# Handheld.net
KiCad netlist of a schematic drawn in EAGLE
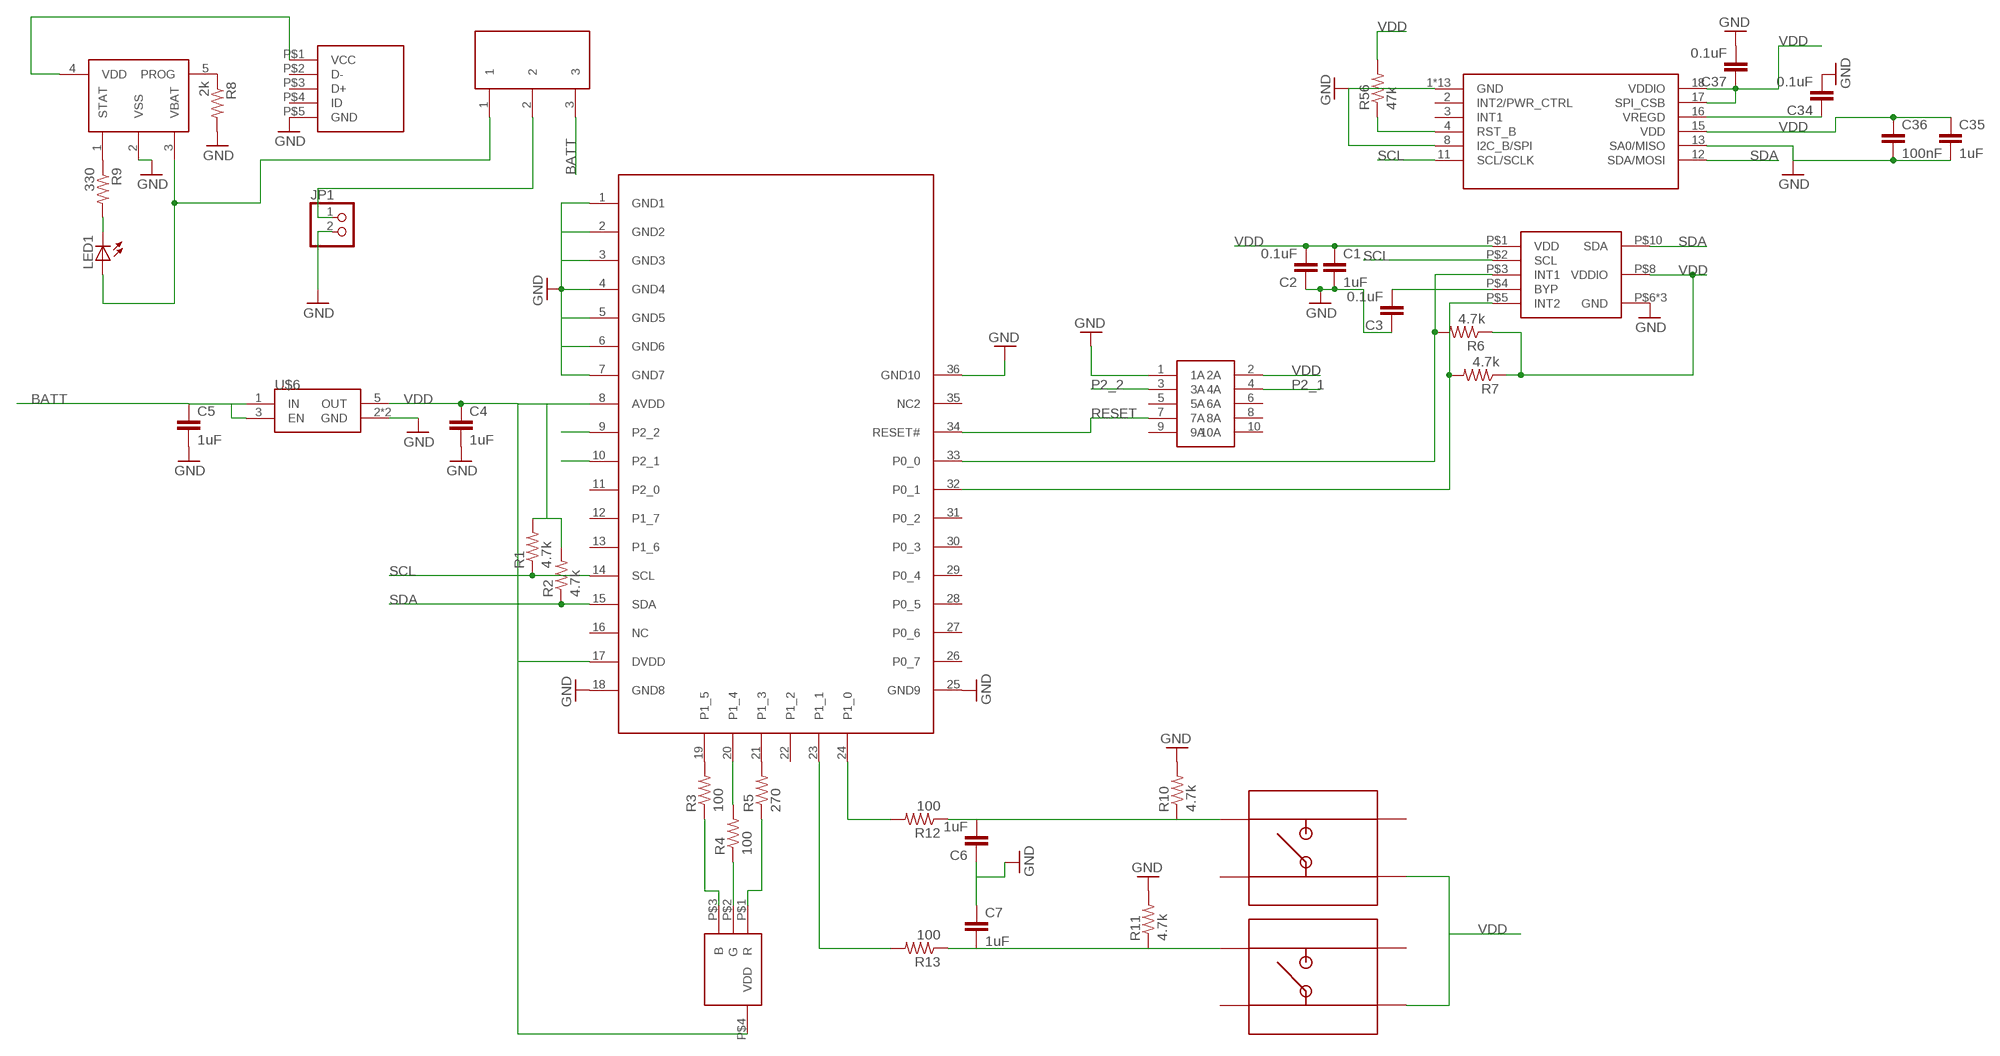
[diagram p0: schematic, sheet 1]

(export (version "E")
  (design (tool "Eeschema 10.0.6"))
  (components
    (comp (ref "C1")
      (value "1uF")
      (footprint "eagle-import:C0402")
      (libsource (lib "eagle-import") (part "C-EUC0402"))
    )
    (comp (ref "C2")
      (value "0.1uF")
      (footprint "eagle-import:C0402")
      (libsource (lib "eagle-import") (part "C-EUC0402"))
    )
    (comp (ref "C3")
      (value "0.1uF")
      (footprint "eagle-import:C0402")
      (libsource (lib "eagle-import") (part "C-EUC0402"))
    )
    (comp (ref "C4")
      (value "1uF")
      (footprint "eagle-import:C0402")
      (libsource (lib "eagle-import") (part "C-EUC0402"))
    )
    (comp (ref "C5")
      (value "1uF")
      (footprint "eagle-import:C0402")
      (libsource (lib "eagle-import") (part "C-EUC0402"))
    )
    (comp (ref "C6")
      (value "1uF")
      (footprint "eagle-import:C0402")
      (libsource (lib "eagle-import") (part "C-EUC0402"))
    )
    (comp (ref "C7")
      (value "1uF")
      (footprint "eagle-import:C0402")
      (libsource (lib "eagle-import") (part "C-EUC0402"))
    )
    (comp (ref "C34")
      (value "0.1uF")
      (footprint "eagle-import:C0402")
      (libsource (lib "eagle-import") (part "C-EUC0402"))
    )
    (comp (ref "C35")
      (value "1uF")
      (footprint "eagle-import:C0402")
      (libsource (lib "eagle-import") (part "C-EUC0402"))
    )
    (comp (ref "C36")
      (value "100nF")
      (footprint "eagle-import:C0402")
      (libsource (lib "eagle-import") (part "C-EUC0402"))
    )
    (comp (ref "C37")
      (value "0.1uF")
      (footprint "eagle-import:C0402")
      (libsource (lib "eagle-import") (part "C-EUC0402"))
    )
    (comp (ref "JP1")
      (value "PINHD-1X2")
      (footprint "eagle-import:1X02")
      (libsource (lib "eagle-import") (part "PINHD-1X2"))
    )
    (comp (ref "LED1")
      (value "LEDCHIPLED_0805")
      (footprint "eagle-import:CHIPLED_0805")
      (libsource (lib "eagle-import") (part "LEDCHIPLED_0805"))
    )
    (comp (ref "R1")
      (value "4.7k")
      (footprint "eagle-import:R0402")
      (libsource (lib "eagle-import") (part "R-US_R0402"))
    )
    (comp (ref "R2")
      (value "4.7k")
      (footprint "eagle-import:R0402")
      (libsource (lib "eagle-import") (part "R-US_R0402"))
    )
    (comp (ref "R3")
      (value "100")
      (footprint "eagle-import:R0402")
      (libsource (lib "eagle-import") (part "R-US_R0402"))
    )
    (comp (ref "R4")
      (value "100")
      (footprint "eagle-import:R0402")
      (libsource (lib "eagle-import") (part "R-US_R0402"))
    )
    (comp (ref "R5")
      (value "270")
      (footprint "eagle-import:R0402")
      (libsource (lib "eagle-import") (part "R-US_R0402"))
    )
    (comp (ref "R6")
      (value "4.7k")
      (footprint "eagle-import:R0402")
      (libsource (lib "eagle-import") (part "R-US_R0402"))
    )
    (comp (ref "R7")
      (value "4.7k")
      (footprint "eagle-import:R0402")
      (libsource (lib "eagle-import") (part "R-US_R0402"))
    )
    (comp (ref "R8")
      (value "2k")
      (footprint "eagle-import:R0402")
      (libsource (lib "eagle-import") (part "R-US_R0402"))
    )
    (comp (ref "R9")
      (value "330")
      (footprint "eagle-import:R0402")
      (libsource (lib "eagle-import") (part "R-US_R0402"))
    )
    (comp (ref "R10")
      (value "4.7k")
      (footprint "eagle-import:R0402")
      (libsource (lib "eagle-import") (part "R-US_R0402"))
    )
    (comp (ref "R11")
      (value "4.7k")
      (footprint "eagle-import:R0402")
      (libsource (lib "eagle-import") (part "R-US_R0402"))
    )
    (comp (ref "R12")
      (value "100")
      (footprint "eagle-import:R0402")
      (libsource (lib "eagle-import") (part "R-US_R0402"))
    )
    (comp (ref "R13")
      (value "100")
      (footprint "eagle-import:R0402")
      (libsource (lib "eagle-import") (part "R-US_R0402"))
    )
    (comp (ref "R56")
      (value "47k")
      (footprint "eagle-import:R0402")
      (libsource (lib "eagle-import") (part "R-US_R0402"))
    )
    (comp (ref "U$1")
      (value "BLE113")
      (footprint "eagle-import:BLUEGIGA")
      (libsource (lib "eagle-import") (part "BLE113"))
    )
    (comp (ref "U$2")
      (value "RIBBON_10POS_MALE")
      (footprint "eagle-import:RIBBON_10POS_MALE")
      (libsource (lib "eagle-import") (part "RIBBON_10POS_MALE"))
    )
    (comp (ref "U$3")
      (value "MMA8653FC")
      (footprint "eagle-import:10-DFN2X2")
      (libsource (lib "eagle-import") (part "MMA8653FC"))
    )
    (comp (ref "U$4")
      (value "MCP73831")
      (footprint "eagle-import:MCP73831")
      (libsource (lib "eagle-import") (part "MCP73831"))
    )
    (comp (ref "U$5")
      (value "MICRO_USB")
      (footprint "eagle-import:MOLEX_USB")
      (libsource (lib "eagle-import") (part "MICRO_USB"))
    )
    (comp (ref "U$6")
      (value "TPS782XX")
      (footprint "eagle-import:SOT23-5L")
      (libsource (lib "eagle-import") (part "TPS782XX"))
    )
    (comp (ref "U$7")
      (value "LTST-C19HE1WT")
      (footprint "eagle-import:LTST-C19HE1WT")
      (libsource (lib "eagle-import") (part "LTST-C19HE1WT"))
    )
    (comp (ref "U$8")
      (value "SMD_TACTILE")
      (footprint "eagle-import:EVQ-Q2U03W")
      (libsource (lib "eagle-import") (part "SMD_TACTILE"))
    )
    (comp (ref "U$9")
      (value "SMD_TACTILE")
      (footprint "eagle-import:EVQ-Q2U03W")
      (libsource (lib "eagle-import") (part "SMD_TACTILE"))
    )
    (comp (ref "U$10")
      (value "SPDT_THRU")
      (footprint "eagle-import:SPDT_THRU")
      (libsource (lib "eagle-import") (part "SPDT_THRU"))
    )
    (comp (ref "U$34")
      (value "FXAS21002")
      (footprint "eagle-import:FXAS21002")
      (libsource (lib "eagle-import") (part "FXAS21002"))
    )
  )
  (nets
    (net (code "1") (name "/BATT") (class "Default")
      (node (ref "C5") (pin "1") (pinfunction "1_1") (pintype "passive"))
      (node (ref "U$10") (pin "3") (pinfunction "3_3") (pintype "bidirectional"))
      (node (ref "U$6") (pin "1") (pinfunction "IN_1") (pintype "bidirectional"))
      (node (ref "U$6") (pin "3") (pinfunction "EN_3") (pintype "bidirectional"))
    )
    (net (code "2") (name "/P2_1") (class "Default")
      (node (ref "U$2") (pin "4") (pinfunction "4A_4") (pintype "bidirectional"))
    )
    (net (code "3") (name "/P2_2") (class "Default")
      (node (ref "U$2") (pin "3") (pinfunction "3A_3") (pintype "bidirectional"))
    )
    (net (code "4") (name "/RESET") (class "Default")
      (node (ref "U$1") (pin "34") (pinfunction "RESET#_34") (pintype "bidirectional"))
      (node (ref "U$2") (pin "7") (pinfunction "7A_7") (pintype "bidirectional"))
    )
    (net (code "5") (name "/SCL") (class "Default")
      (node (ref "R1") (pin "1") (pinfunction "1_1") (pintype "passive"))
      (node (ref "U$1") (pin "14") (pinfunction "SCL_14") (pintype "bidirectional"))
      (node (ref "U$3") (pin "P$2") (pinfunction "SCL_P$2") (pintype "bidirectional"))
      (node (ref "U$34") (pin "11") (pinfunction "SCL/SCLK_11") (pintype "bidirectional"))
    )
    (net (code "6") (name "/SDA") (class "Default")
      (node (ref "R2") (pin "1") (pinfunction "1_1") (pintype "passive"))
      (node (ref "U$1") (pin "15") (pinfunction "SDA_15") (pintype "bidirectional"))
      (node (ref "U$3") (pin "P$10") (pinfunction "SDA_P$10") (pintype "bidirectional"))
      (node (ref "U$34") (pin "12") (pinfunction "SDA/MOSI_12") (pintype "bidirectional"))
    )
    (net (code "7") (name "/VDD") (class "Default")
      (node (ref "C1") (pin "1") (pinfunction "1_1") (pintype "passive"))
      (node (ref "C2") (pin "2") (pinfunction "2_2") (pintype "passive"))
      (node (ref "C35") (pin "1") (pinfunction "1_1") (pintype "passive"))
      (node (ref "C36") (pin "1") (pinfunction "1_1") (pintype "passive"))
      (node (ref "C37") (pin "1") (pinfunction "1_1") (pintype "passive"))
      (node (ref "C4") (pin "1") (pinfunction "1_1") (pintype "passive"))
      (node (ref "R1") (pin "2") (pinfunction "2_2") (pintype "passive"))
      (node (ref "R2") (pin "2") (pinfunction "2_2") (pintype "passive"))
      (node (ref "R56") (pin "2") (pinfunction "2_2") (pintype "passive"))
      (node (ref "R6") (pin "1") (pinfunction "1_1") (pintype "passive"))
      (node (ref "R7") (pin "1") (pinfunction "1_1") (pintype "passive"))
      (node (ref "U$1") (pin "17") (pinfunction "DVDD_17") (pintype "bidirectional"))
      (node (ref "U$1") (pin "8") (pinfunction "AVDD_8") (pintype "bidirectional"))
      (node (ref "U$2") (pin "2") (pinfunction "2A_2") (pintype "bidirectional"))
      (node (ref "U$3") (pin "P$1") (pinfunction "VDD_P$1") (pintype "bidirectional"))
      (node (ref "U$3") (pin "P$8") (pinfunction "VDDIO_P$8") (pintype "bidirectional"))
      (node (ref "U$34") (pin "15") (pinfunction "VDD_15") (pintype "bidirectional"))
      (node (ref "U$34") (pin "17") (pinfunction "SPI_CSB_17") (pintype "bidirectional"))
      (node (ref "U$34") (pin "18") (pinfunction "VDDIO_18") (pintype "bidirectional"))
      (node (ref "U$6") (pin "5") (pinfunction "OUT_5") (pintype "bidirectional"))
      (node (ref "U$7") (pin "P$4") (pinfunction "VDD_P$4") (pintype "bidirectional"))
      (node (ref "U$8") (pin "4") (pinfunction "4_4") (pintype "bidirectional"))
      (node (ref "U$9") (pin "4") (pinfunction "4_4") (pintype "bidirectional"))
    )
    (net (code "8") (name "GND") (class "Default")
      (node (ref "C1") (pin "2") (pinfunction "2_2") (pintype "passive"))
      (node (ref "C2") (pin "1") (pinfunction "1_1") (pintype "passive"))
      (node (ref "C3") (pin "1") (pinfunction "1_1") (pintype "passive"))
      (node (ref "C34") (pin "2") (pinfunction "2_2") (pintype "passive"))
      (node (ref "C35") (pin "2") (pinfunction "2_2") (pintype "passive"))
      (node (ref "C36") (pin "2") (pinfunction "2_2") (pintype "passive"))
      (node (ref "C37") (pin "2") (pinfunction "2_2") (pintype "passive"))
      (node (ref "C4") (pin "2") (pinfunction "2_2") (pintype "passive"))
      (node (ref "C5") (pin "2") (pinfunction "2_2") (pintype "passive"))
      (node (ref "C6") (pin "1") (pinfunction "1_1") (pintype "passive"))
      (node (ref "C7") (pin "1") (pinfunction "1_1") (pintype "passive"))
      (node (ref "JP1") (pin "2") (pinfunction "2_2") (pintype "passive"))
      (node (ref "R10") (pin "2") (pinfunction "2_2") (pintype "passive"))
      (node (ref "R11") (pin "2") (pinfunction "2_2") (pintype "passive"))
      (node (ref "R8") (pin "2") (pinfunction "2_2") (pintype "passive"))
      (node (ref "U$1") (pin "1") (pinfunction "GND1_1") (pintype "bidirectional"))
      (node (ref "U$1") (pin "18") (pinfunction "GND8_18") (pintype "bidirectional"))
      (node (ref "U$1") (pin "2") (pinfunction "GND2_2") (pintype "bidirectional"))
      (node (ref "U$1") (pin "25") (pinfunction "GND9_25") (pintype "bidirectional"))
      (node (ref "U$1") (pin "3") (pinfunction "GND3_3") (pintype "bidirectional"))
      (node (ref "U$1") (pin "36") (pinfunction "GND10_36") (pintype "bidirectional"))
      (node (ref "U$1") (pin "4") (pinfunction "GND4_4") (pintype "bidirectional"))
      (node (ref "U$1") (pin "5") (pinfunction "GND5_5") (pintype "bidirectional"))
      (node (ref "U$1") (pin "6") (pinfunction "GND6_6") (pintype "bidirectional"))
      (node (ref "U$1") (pin "7") (pinfunction "GND7_7") (pintype "bidirectional"))
      (node (ref "U$2") (pin "1") (pinfunction "1A_1") (pintype "bidirectional"))
      (node (ref "U$3") (pin "P$6") (pinfunction "GND_P$6") (pintype "bidirectional"))
      (node (ref "U$3") (pin "P$7") (pinfunction "GND_P$7") (pintype "bidirectional"))
      (node (ref "U$3") (pin "P$9") (pinfunction "GND_P$9") (pintype "bidirectional"))
      (node (ref "U$34") (pin "1") (pinfunction "GND_1") (pintype "bidirectional"))
      (node (ref "U$34") (pin "10") (pinfunction "GND_10") (pintype "bidirectional"))
      (node (ref "U$34") (pin "13") (pinfunction "SA0/MISO_13") (pintype "bidirectional"))
      (node (ref "U$34") (pin "14") (pinfunction "GND_14") (pintype "bidirectional"))
      (node (ref "U$34") (pin "19") (pinfunction "GND_19") (pintype "bidirectional"))
      (node (ref "U$34") (pin "20") (pinfunction "GND_20") (pintype "bidirectional"))
      (node (ref "U$34") (pin "21") (pinfunction "GND_21") (pintype "bidirectional"))
      (node (ref "U$34") (pin "22") (pinfunction "GND_22") (pintype "bidirectional"))
      (node (ref "U$34") (pin "23") (pinfunction "GND_23") (pintype "bidirectional"))
      (node (ref "U$34") (pin "24") (pinfunction "GND_24") (pintype "bidirectional"))
      (node (ref "U$34") (pin "5") (pinfunction "GND_5") (pintype "bidirectional"))
      (node (ref "U$34") (pin "6") (pinfunction "GND_6") (pintype "bidirectional"))
      (node (ref "U$34") (pin "7") (pinfunction "GND_7") (pintype "bidirectional"))
      (node (ref "U$34") (pin "8") (pinfunction "I2C_B/SPI_8") (pintype "bidirectional"))
      (node (ref "U$34") (pin "9") (pinfunction "GND_9") (pintype "bidirectional"))
      (node (ref "U$4") (pin "2") (pinfunction "VSS_2") (pintype "bidirectional"))
      (node (ref "U$5") (pin "P$5") (pinfunction "GND_P$5") (pintype "bidirectional"))
      (node (ref "U$6") (pin "2") (pinfunction "GND_2") (pintype "bidirectional"))
      (node (ref "U$6") (pin "4") (pinfunction "GND_4") (pintype "bidirectional"))
    )
    (net (code "9") (name "Net-(C6-Pad2)") (class "Default")
      (node (ref "C6") (pin "2") (pinfunction "2_2") (pintype "passive"))
      (node (ref "R10") (pin "1") (pinfunction "1_1") (pintype "passive"))
      (node (ref "R12") (pin "1") (pinfunction "1_1") (pintype "passive"))
      (node (ref "U$8") (pin "1") (pinfunction "1_1") (pintype "bidirectional"))
    )
    (net (code "10") (name "Net-(C7-Pad2)") (class "Default")
      (node (ref "C7") (pin "2") (pinfunction "2_2") (pintype "passive"))
      (node (ref "R11") (pin "1") (pinfunction "1_1") (pintype "passive"))
      (node (ref "R13") (pin "1") (pinfunction "1_1") (pintype "passive"))
      (node (ref "U$9") (pin "1") (pinfunction "1_1") (pintype "bidirectional"))
    )
    (net (code "11") (name "Net-(JP1-Pad1)") (class "Default")
      (node (ref "JP1") (pin "1") (pinfunction "1_1") (pintype "passive"))
      (node (ref "U$10") (pin "2") (pinfunction "2_2") (pintype "bidirectional"))
    )
    (net (code "12") (name "Net-(LED1-PadC)") (class "Default")
      (node (ref "LED1") (pin "C") (pinfunction "C_C") (pintype "passive"))
      (node (ref "R9") (pin "2") (pinfunction "2_2") (pintype "passive"))
    )
    (net (code "13") (name "Net-(U$1-P0_0)") (class "Default")
      (node (ref "R6") (pin "2") (pinfunction "2_2") (pintype "passive"))
      (node (ref "U$1") (pin "33") (pinfunction "P0_0_33") (pintype "bidirectional"))
      (node (ref "U$3") (pin "P$3") (pinfunction "INT1_P$3") (pintype "bidirectional"))
    )
    (net (code "14") (name "Net-(U$1-P0_1)") (class "Default")
      (node (ref "R7") (pin "2") (pinfunction "2_2") (pintype "passive"))
      (node (ref "U$1") (pin "32") (pinfunction "P0_1_32") (pintype "bidirectional"))
      (node (ref "U$3") (pin "P$5") (pinfunction "INT2_P$5") (pintype "bidirectional"))
    )
    (net (code "15") (name "Net-(U$1-P1_0)") (class "Default")
      (node (ref "R12") (pin "2") (pinfunction "2_2") (pintype "passive"))
      (node (ref "U$1") (pin "24") (pinfunction "P1_0_24") (pintype "bidirectional"))
    )
    (net (code "16") (name "Net-(U$1-P1_1)") (class "Default")
      (node (ref "R13") (pin "2") (pinfunction "2_2") (pintype "passive"))
      (node (ref "U$1") (pin "23") (pinfunction "P1_1_23") (pintype "bidirectional"))
    )
    (net (code "17") (name "Net-(U$1-P1_3)") (class "Default")
      (node (ref "R5") (pin "2") (pinfunction "2_2") (pintype "passive"))
      (node (ref "U$1") (pin "21") (pinfunction "P1_3_21") (pintype "bidirectional"))
    )
    (net (code "18") (name "Net-(U$1-P1_4)") (class "Default")
      (node (ref "R4") (pin "2") (pinfunction "2_2") (pintype "passive"))
      (node (ref "U$1") (pin "20") (pinfunction "P1_4_20") (pintype "bidirectional"))
    )
    (net (code "19") (name "Net-(U$1-P1_5)") (class "Default")
      (node (ref "R3") (pin "2") (pinfunction "2_2") (pintype "passive"))
      (node (ref "U$1") (pin "19") (pinfunction "P1_5_19") (pintype "bidirectional"))
    )
    (net (code "20") (name "Net-(U$3-BYP)") (class "Default")
      (node (ref "C3") (pin "2") (pinfunction "2_2") (pintype "passive"))
      (node (ref "U$3") (pin "P$4") (pinfunction "BYP_P$4") (pintype "bidirectional"))
    )
    (net (code "21") (name "Net-(U$4-PROG)") (class "Default")
      (node (ref "R8") (pin "1") (pinfunction "1_1") (pintype "passive"))
      (node (ref "U$4") (pin "5") (pinfunction "PROG_5") (pintype "bidirectional"))
    )
    (net (code "22") (name "Net-(U$4-STAT)") (class "Default")
      (node (ref "R9") (pin "1") (pinfunction "1_1") (pintype "passive"))
      (node (ref "U$4") (pin "1") (pinfunction "STAT_1") (pintype "bidirectional"))
    )
    (net (code "23") (name "Net-(U$4-VBAT)") (class "Default")
      (node (ref "LED1") (pin "A") (pinfunction "A_A") (pintype "passive"))
      (node (ref "U$10") (pin "1") (pinfunction "1_1") (pintype "bidirectional"))
      (node (ref "U$4") (pin "3") (pinfunction "VBAT_3") (pintype "bidirectional"))
    )
    (net (code "24") (name "Net-(U$4-VDD)") (class "Default")
      (node (ref "U$4") (pin "4") (pinfunction "VDD_4") (pintype "bidirectional"))
      (node (ref "U$5") (pin "P$1") (pinfunction "VCC_P$1") (pintype "bidirectional"))
    )
    (net (code "25") (name "Net-(U$7-B)") (class "Default")
      (node (ref "R3") (pin "1") (pinfunction "1_1") (pintype "passive"))
      (node (ref "U$7") (pin "P$3") (pinfunction "B_P$3") (pintype "bidirectional"))
    )
    (net (code "26") (name "Net-(U$7-G)") (class "Default")
      (node (ref "R4") (pin "1") (pinfunction "1_1") (pintype "passive"))
      (node (ref "U$7") (pin "P$2") (pinfunction "G_P$2") (pintype "bidirectional"))
    )
    (net (code "27") (name "Net-(U$7-R)") (class "Default")
      (node (ref "R5") (pin "1") (pinfunction "1_1") (pintype "passive"))
      (node (ref "U$7") (pin "P$1") (pinfunction "R_P$1") (pintype "bidirectional"))
    )
    (net (code "28") (name "Net-(U$34-RST_B)") (class "Default")
      (node (ref "R56") (pin "1") (pinfunction "1_1") (pintype "passive"))
      (node (ref "U$34") (pin "4") (pinfunction "RST_B_4") (pintype "bidirectional"))
    )
    (net (code "29") (name "Net-(U$34-VREGD)") (class "Default")
      (node (ref "C34") (pin "1") (pinfunction "1_1") (pintype "passive"))
      (node (ref "U$34") (pin "16") (pinfunction "VREGD_16") (pintype "bidirectional"))
    )
    (net (code "30") (name "unconnected-(U$1-NC-Pad16)") (class "Default")
      (node (ref "U$1") (pin "16") (pinfunction "NC_16") (pintype "bidirectional"))
    )
    (net (code "31") (name "unconnected-(U$1-NC2-Pad35)") (class "Default")
      (node (ref "U$1") (pin "35") (pinfunction "NC2_35") (pintype "bidirectional"))
    )
    (net (code "32") (name "unconnected-(U$1-P0_2-Pad31)") (class "Default")
      (node (ref "U$1") (pin "31") (pinfunction "P0_2_31") (pintype "bidirectional"))
    )
    (net (code "33") (name "unconnected-(U$1-P0_3-Pad30)") (class "Default")
      (node (ref "U$1") (pin "30") (pinfunction "P0_3_30") (pintype "bidirectional"))
    )
    (net (code "34") (name "unconnected-(U$1-P0_4-Pad29)") (class "Default")
      (node (ref "U$1") (pin "29") (pinfunction "P0_4_29") (pintype "bidirectional"))
    )
    (net (code "35") (name "unconnected-(U$1-P0_5-Pad28)") (class "Default")
      (node (ref "U$1") (pin "28") (pinfunction "P0_5_28") (pintype "bidirectional"))
    )
    (net (code "36") (name "unconnected-(U$1-P0_6-Pad27)") (class "Default")
      (node (ref "U$1") (pin "27") (pinfunction "P0_6_27") (pintype "bidirectional"))
    )
    (net (code "37") (name "unconnected-(U$1-P0_7-Pad26)") (class "Default")
      (node (ref "U$1") (pin "26") (pinfunction "P0_7_26") (pintype "bidirectional"))
    )
    (net (code "38") (name "unconnected-(U$1-P1_2-Pad22)") (class "Default")
      (node (ref "U$1") (pin "22") (pinfunction "P1_2_22") (pintype "bidirectional"))
    )
    (net (code "39") (name "unconnected-(U$1-P1_6-Pad13)") (class "Default")
      (node (ref "U$1") (pin "13") (pinfunction "P1_6_13") (pintype "bidirectional"))
    )
    (net (code "40") (name "unconnected-(U$1-P1_7-Pad12)") (class "Default")
      (node (ref "U$1") (pin "12") (pinfunction "P1_7_12") (pintype "bidirectional"))
    )
    (net (code "41") (name "unconnected-(U$1-P2_0-Pad11)") (class "Default")
      (node (ref "U$1") (pin "11") (pinfunction "P2_0_11") (pintype "bidirectional"))
    )
    (net (code "42") (name "unconnected-(U$1-P2_1-Pad10)") (class "Default")
      (node (ref "U$1") (pin "10") (pinfunction "P2_1_10") (pintype "bidirectional"))
    )
    (net (code "43") (name "unconnected-(U$1-P2_2-Pad9)") (class "Default")
      (node (ref "U$1") (pin "9") (pinfunction "P2_2_9") (pintype "bidirectional"))
    )
    (net (code "44") (name "unconnected-(U$2-5A-Pad5)") (class "Default")
      (node (ref "U$2") (pin "5") (pinfunction "5A_5") (pintype "bidirectional"))
    )
    (net (code "45") (name "unconnected-(U$2-6A-Pad6)") (class "Default")
      (node (ref "U$2") (pin "6") (pinfunction "6A_6") (pintype "bidirectional"))
    )
    (net (code "46") (name "unconnected-(U$2-8A-Pad8)") (class "Default")
      (node (ref "U$2") (pin "8") (pinfunction "8A_8") (pintype "bidirectional"))
    )
    (net (code "47") (name "unconnected-(U$2-9A-Pad9)") (class "Default")
      (node (ref "U$2") (pin "9") (pinfunction "9A_9") (pintype "bidirectional"))
    )
    (net (code "48") (name "unconnected-(U$2-10A-Pad10)") (class "Default")
      (node (ref "U$2") (pin "10") (pinfunction "10A_10") (pintype "bidirectional"))
    )
    (net (code "49") (name "unconnected-(U$5-D+-PadP$3)") (class "Default")
      (node (ref "U$5") (pin "P$3") (pinfunction "D+_P$3") (pintype "bidirectional"))
    )
    (net (code "50") (name "unconnected-(U$5-D--PadP$2)") (class "Default")
      (node (ref "U$5") (pin "P$2") (pinfunction "D-_P$2") (pintype "bidirectional"))
    )
    (net (code "51") (name "unconnected-(U$5-ID-PadP$4)") (class "Default")
      (node (ref "U$5") (pin "P$4") (pinfunction "ID_P$4") (pintype "bidirectional"))
    )
    (net (code "52") (name "unconnected-(U$8-Pad2)") (class "Default")
      (node (ref "U$8") (pin "2") (pinfunction "2_2") (pintype "bidirectional"))
    )
    (net (code "53") (name "unconnected-(U$8-Pad3)") (class "Default")
      (node (ref "U$8") (pin "3") (pinfunction "3_3") (pintype "bidirectional"))
    )
    (net (code "54") (name "unconnected-(U$9-Pad2)") (class "Default")
      (node (ref "U$9") (pin "2") (pinfunction "2_2") (pintype "bidirectional"))
    )
    (net (code "55") (name "unconnected-(U$9-Pad3)") (class "Default")
      (node (ref "U$9") (pin "3") (pinfunction "3_3") (pintype "bidirectional"))
    )
    (net (code "56") (name "unconnected-(U$34-INT1-Pad3)") (class "Default")
      (node (ref "U$34") (pin "3") (pinfunction "INT1_3") (pintype "bidirectional"))
    )
    (net (code "57") (name "unconnected-(U$34-INT2{slash}PWR_CTRL-Pad2)") (class "Default")
      (node (ref "U$34") (pin "2") (pinfunction "INT2/PWR_CTRL_2") (pintype "bidirectional"))
    )
  )
)
